# Wooby.net
KiCad netlist of a schematic drawn in EAGLE
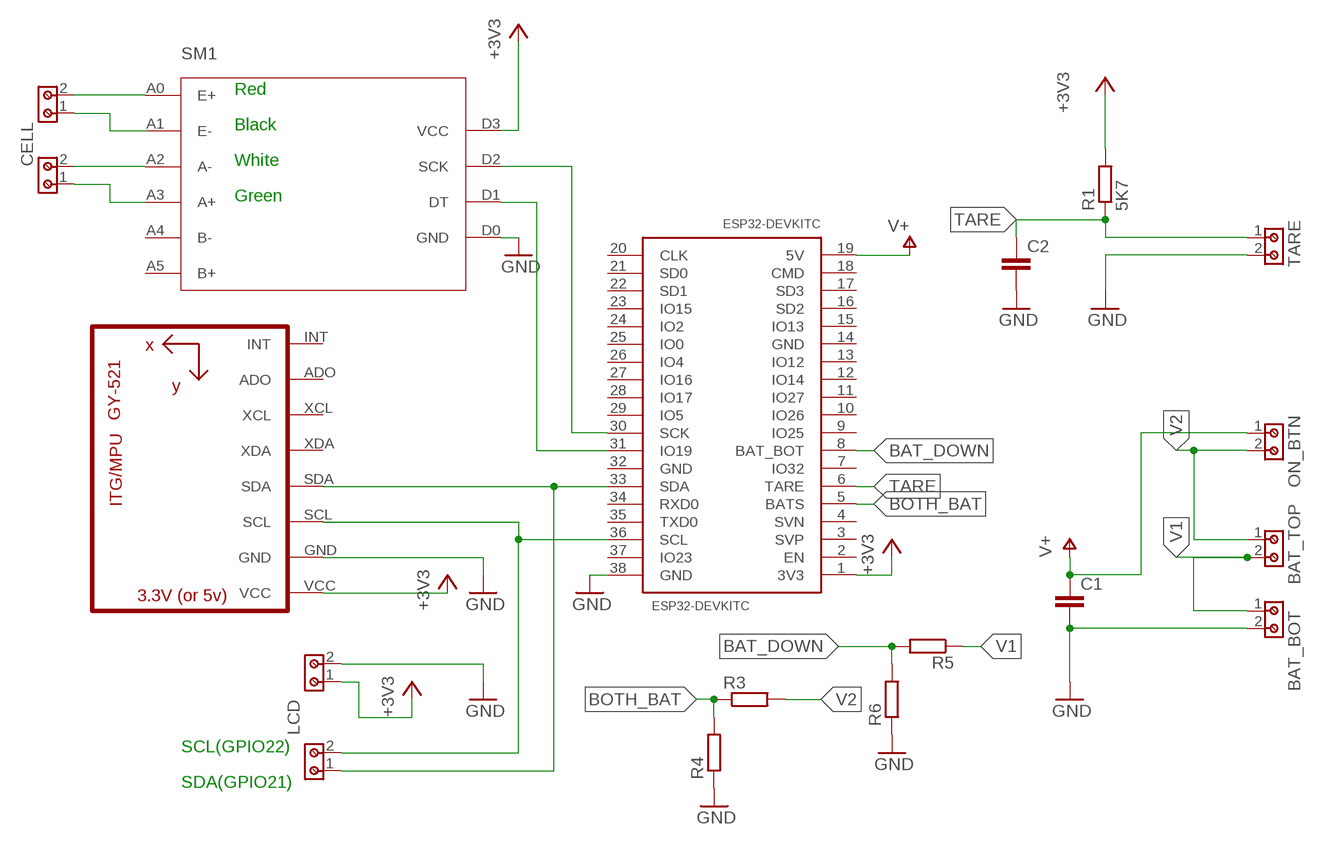
[diagram p0: schematic, sheet 1]

(export (version "E")
  (design (tool "Eeschema 10.0.6"))
  (components
    (comp (ref "BAT_BOT")
      (value "691210910002")
      (footprint "eagle-import:691210910002")
      (fields (field (name "MF") "Würth Elektronik"))
      (libsource (lib "eagle-import") (part "691210910002"))
    )
    (comp (ref "BAT_TOP")
      (value "691210910002")
      (footprint "eagle-import:691210910002")
      (fields (field (name "MF") "Würth Elektronik"))
      (libsource (lib "eagle-import") (part "691210910002"))
    )
    (comp (ref "C1")
      (value "C5/3")
      (footprint "eagle-import:C5B3")
      (libsource (lib "eagle-import") (part "C5/3"))
    )
    (comp (ref "C2")
      (value "C5/3")
      (footprint "eagle-import:C5B3")
      (libsource (lib "eagle-import") (part "C5/3"))
    )
    (comp (ref "CELL")
      (value "691210910002")
      (footprint "eagle-import:691210910002")
      (fields (field (name "MF") "Würth Elektronik"))
      (libsource (lib "eagle-import") (part "691210910002"))
    )
    (comp (ref "ESP32-DEVKITC")
      (value "ESP32DEVKITC")
      (footprint "eagle-import:ESP32-DEVKITC")
      (libsource (lib "eagle-import") (part "ESP32DEVKITC"))
    )
    (comp (ref "J2")
      (value "691210910002")
      (footprint "eagle-import:691210910002")
      (fields (field (name "MF") "Würth Elektronik"))
      (libsource (lib "eagle-import") (part "691210910002"))
    )
    (comp (ref "J5")
      (value "691210910002")
      (footprint "eagle-import:691210910002")
      (fields (field (name "MF") "Würth Elektronik"))
      (libsource (lib "eagle-import") (part "691210910002"))
    )
    (comp (ref "LCD")
      (value "691210910002")
      (footprint "eagle-import:691210910002")
      (fields (field (name "MF") "Würth Elektronik"))
      (libsource (lib "eagle-import") (part "691210910002"))
    )
    (comp (ref "ON_BTN")
      (value "691210910002")
      (footprint "eagle-import:691210910002")
      (fields (field (name "MF") "Würth Elektronik"))
      (libsource (lib "eagle-import") (part "691210910002"))
    )
    (comp (ref "R1")
      (value "5K7")
      (footprint "eagle-import:0207_10")
      (libsource (lib "eagle-import") (part "R-EU_0207/10"))
    )
    (comp (ref "R3")
      (value "R-EU_0207/10")
      (footprint "eagle-import:0207_10")
      (libsource (lib "eagle-import") (part "R-EU_0207/10"))
    )
    (comp (ref "R4")
      (value "R-EU_0207/10")
      (footprint "eagle-import:0207_10")
      (libsource (lib "eagle-import") (part "R-EU_0207/10"))
    )
    (comp (ref "R5")
      (value "R-EU_0207/10")
      (footprint "eagle-import:0207_10")
      (libsource (lib "eagle-import") (part "R-EU_0207/10"))
    )
    (comp (ref "R6")
      (value "R-EU_0207/10")
      (footprint "eagle-import:0207_10")
      (libsource (lib "eagle-import") (part "R-EU_0207/10"))
    )
    (comp (ref "SM1")
      (value "HX711")
      (footprint "eagle-import:HX711")
      (libsource (lib "eagle-import") (part "HX711"))
    )
    (comp (ref "TARE")
      (value "691210910002")
      (footprint "eagle-import:691210910002")
      (fields (field (name "MF") "Würth Elektronik"))
      (libsource (lib "eagle-import") (part "691210910002"))
    )
    (comp (ref "U1")
      (value "GY-521MPU6050")
      (footprint "eagle-import:GY-521")
      (libsource (lib "eagle-import") (part "GY-521MPU6050"))
    )
  )
  (nets
    (net (code "1") (name "+3V3") (class "Default")
      (node (ref "ESP32-DEVKITC") (pin "1") (pinfunction "3V3_1") (pintype "bidirectional"))
      (node (ref "LCD") (pin "1") (pinfunction "1_1") (pintype "passive"))
      (node (ref "R1") (pin "2") (pinfunction "2_2") (pintype "passive"))
      (node (ref "SM1") (pin "D3") (pinfunction "VCC_D3") (pintype "bidirectional"))
      (node (ref "U1") (pin "VCC") (pinfunction "VCC_VCC") (pintype "bidirectional"))
    )
    (net (code "2") (name "BAT_DOWN") (class "Default")
      (node (ref "ESP32-DEVKITC") (pin "8") (pinfunction "BAT_BOT_8") (pintype "bidirectional"))
      (node (ref "R5") (pin "2") (pinfunction "2_2") (pintype "passive"))
      (node (ref "R6") (pin "2") (pinfunction "2_2") (pintype "passive"))
    )
    (net (code "3") (name "BOTH_BAT") (class "Default")
      (node (ref "ESP32-DEVKITC") (pin "5") (pinfunction "BATS_5") (pintype "bidirectional"))
      (node (ref "R3") (pin "1") (pinfunction "1_1") (pintype "passive"))
      (node (ref "R4") (pin "2") (pinfunction "2_2") (pintype "passive"))
    )
    (net (code "4") (name "GND") (class "Default")
      (node (ref "BAT_BOT") (pin "2") (pinfunction "2_2") (pintype "passive"))
      (node (ref "C1") (pin "2") (pinfunction "2_2") (pintype "passive"))
      (node (ref "C2") (pin "2") (pinfunction "2_2") (pintype "passive"))
      (node (ref "ESP32-DEVKITC") (pin "38") (pinfunction "GND_38") (pintype "bidirectional"))
      (node (ref "LCD") (pin "2") (pinfunction "2_2") (pintype "passive"))
      (node (ref "R4") (pin "1") (pinfunction "1_1") (pintype "passive"))
      (node (ref "R6") (pin "1") (pinfunction "1_1") (pintype "passive"))
      (node (ref "SM1") (pin "D0") (pinfunction "GND_D0") (pintype "bidirectional"))
      (node (ref "TARE") (pin "2") (pinfunction "2_2") (pintype "passive"))
      (node (ref "U1") (pin "GND") (pinfunction "GND_GND") (pintype "bidirectional"))
    )
    (net (code "5") (name "Net-(ESP32-DEVKITC-IO19)") (class "Default")
      (node (ref "ESP32-DEVKITC") (pin "31") (pinfunction "IO19_31") (pintype "bidirectional"))
      (node (ref "SM1") (pin "D1") (pinfunction "DT_D1") (pintype "bidirectional"))
    )
    (net (code "6") (name "Net-(ESP32-DEVKITC-SCK)") (class "Default")
      (node (ref "ESP32-DEVKITC") (pin "30") (pinfunction "SCK_30") (pintype "bidirectional"))
      (node (ref "SM1") (pin "D2") (pinfunction "SCK_D2") (pintype "bidirectional"))
    )
    (net (code "7") (name "Net-(ESP32-DEVKITC-SCL)") (class "Default")
      (node (ref "ESP32-DEVKITC") (pin "36") (pinfunction "SCL_36") (pintype "bidirectional"))
      (node (ref "J2") (pin "2") (pinfunction "2_2") (pintype "passive"))
      (node (ref "U1") (pin "SCL") (pinfunction "SCL_SCL") (pintype "bidirectional"))
    )
    (net (code "8") (name "Net-(ESP32-DEVKITC-SDA)") (class "Default")
      (node (ref "ESP32-DEVKITC") (pin "33") (pinfunction "SDA_33") (pintype "bidirectional"))
      (node (ref "J2") (pin "1") (pinfunction "1_1") (pintype "passive"))
      (node (ref "U1") (pin "SDA") (pinfunction "SDA_SDA") (pintype "bidirectional"))
    )
    (net (code "9") (name "Net-(SM1-A+)") (class "Default")
      (node (ref "J5") (pin "1") (pinfunction "1_1") (pintype "passive"))
      (node (ref "SM1") (pin "A3") (pinfunction "A+_A3") (pintype "bidirectional"))
    )
    (net (code "10") (name "Net-(SM1-A-)") (class "Default")
      (node (ref "J5") (pin "2") (pinfunction "2_2") (pintype "passive"))
      (node (ref "SM1") (pin "A2") (pinfunction "A-_A2") (pintype "bidirectional"))
    )
    (net (code "11") (name "Net-(SM1-E+)") (class "Default")
      (node (ref "CELL") (pin "2") (pinfunction "2_2") (pintype "passive"))
      (node (ref "SM1") (pin "A0") (pinfunction "E+_A0") (pintype "bidirectional"))
    )
    (net (code "12") (name "Net-(SM1-E-)") (class "Default")
      (node (ref "CELL") (pin "1") (pinfunction "1_1") (pintype "passive"))
      (node (ref "SM1") (pin "A1") (pinfunction "E-_A1") (pintype "bidirectional"))
    )
    (net (code "13") (name "TARE") (class "Default")
      (node (ref "C2") (pin "1") (pinfunction "1_1") (pintype "passive"))
      (node (ref "ESP32-DEVKITC") (pin "6") (pinfunction "TARE_6") (pintype "bidirectional"))
      (node (ref "R1") (pin "1") (pinfunction "1_1") (pintype "passive"))
      (node (ref "TARE") (pin "1") (pinfunction "1_1") (pintype "passive"))
    )
    (net (code "14") (name "V+") (class "Default")
      (node (ref "C1") (pin "1") (pinfunction "1_1") (pintype "passive"))
      (node (ref "ESP32-DEVKITC") (pin "19") (pinfunction "5V_19") (pintype "bidirectional"))
      (node (ref "ON_BTN") (pin "1") (pinfunction "1_1") (pintype "passive"))
    )
    (net (code "15") (name "V1") (class "Default")
      (node (ref "BAT_BOT") (pin "1") (pinfunction "1_1") (pintype "passive"))
      (node (ref "BAT_TOP") (pin "2") (pinfunction "2_2") (pintype "passive"))
      (node (ref "R5") (pin "1") (pinfunction "1_1") (pintype "passive"))
    )
    (net (code "16") (name "V2") (class "Default")
      (node (ref "BAT_TOP") (pin "1") (pinfunction "1_1") (pintype "passive"))
      (node (ref "ON_BTN") (pin "2") (pinfunction "2_2") (pintype "passive"))
      (node (ref "R3") (pin "2") (pinfunction "2_2") (pintype "passive"))
    )
    (net (code "17") (name "unconnected-(ESP32-DEVKITC-CLK-Pad20)") (class "Default")
      (node (ref "ESP32-DEVKITC") (pin "20") (pinfunction "CLK_20") (pintype "bidirectional"))
    )
    (net (code "18") (name "unconnected-(ESP32-DEVKITC-CMD-Pad18)") (class "Default")
      (node (ref "ESP32-DEVKITC") (pin "18") (pinfunction "CMD_18") (pintype "bidirectional"))
    )
    (net (code "19") (name "unconnected-(ESP32-DEVKITC-EN-Pad2)") (class "Default")
      (node (ref "ESP32-DEVKITC") (pin "2") (pinfunction "EN_2") (pintype "bidirectional"))
    )
    (net (code "20") (name "unconnected-(ESP32-DEVKITC-GND-Pad14)") (class "Default")
      (node (ref "ESP32-DEVKITC") (pin "14") (pinfunction "GND_14") (pintype "bidirectional"))
    )
    (net (code "21") (name "unconnected-(ESP32-DEVKITC-GND-Pad32)") (class "Default")
      (node (ref "ESP32-DEVKITC") (pin "32") (pinfunction "GND_32") (pintype "bidirectional"))
    )
    (net (code "22") (name "unconnected-(ESP32-DEVKITC-IO0-Pad25)") (class "Default")
      (node (ref "ESP32-DEVKITC") (pin "25") (pinfunction "IO0_25") (pintype "bidirectional"))
    )
    (net (code "23") (name "unconnected-(ESP32-DEVKITC-IO2-Pad24)") (class "Default")
      (node (ref "ESP32-DEVKITC") (pin "24") (pinfunction "IO2_24") (pintype "bidirectional"))
    )
    (net (code "24") (name "unconnected-(ESP32-DEVKITC-IO4-Pad26)") (class "Default")
      (node (ref "ESP32-DEVKITC") (pin "26") (pinfunction "IO4_26") (pintype "bidirectional"))
    )
    (net (code "25") (name "unconnected-(ESP32-DEVKITC-IO5-Pad29)") (class "Default")
      (node (ref "ESP32-DEVKITC") (pin "29") (pinfunction "IO5_29") (pintype "bidirectional"))
    )
    (net (code "26") (name "unconnected-(ESP32-DEVKITC-IO12-Pad13)") (class "Default")
      (node (ref "ESP32-DEVKITC") (pin "13") (pinfunction "IO12_13") (pintype "bidirectional"))
    )
    (net (code "27") (name "unconnected-(ESP32-DEVKITC-IO13-Pad15)") (class "Default")
      (node (ref "ESP32-DEVKITC") (pin "15") (pinfunction "IO13_15") (pintype "bidirectional"))
    )
    (net (code "28") (name "unconnected-(ESP32-DEVKITC-IO14-Pad12)") (class "Default")
      (node (ref "ESP32-DEVKITC") (pin "12") (pinfunction "IO14_12") (pintype "bidirectional"))
    )
    (net (code "29") (name "unconnected-(ESP32-DEVKITC-IO15-Pad23)") (class "Default")
      (node (ref "ESP32-DEVKITC") (pin "23") (pinfunction "IO15_23") (pintype "bidirectional"))
    )
    (net (code "30") (name "unconnected-(ESP32-DEVKITC-IO16-Pad27)") (class "Default")
      (node (ref "ESP32-DEVKITC") (pin "27") (pinfunction "IO16_27") (pintype "bidirectional"))
    )
    (net (code "31") (name "unconnected-(ESP32-DEVKITC-IO17-Pad28)") (class "Default")
      (node (ref "ESP32-DEVKITC") (pin "28") (pinfunction "IO17_28") (pintype "bidirectional"))
    )
    (net (code "32") (name "unconnected-(ESP32-DEVKITC-IO23-Pad37)") (class "Default")
      (node (ref "ESP32-DEVKITC") (pin "37") (pinfunction "IO23_37") (pintype "bidirectional"))
    )
    (net (code "33") (name "unconnected-(ESP32-DEVKITC-IO25-Pad9)") (class "Default")
      (node (ref "ESP32-DEVKITC") (pin "9") (pinfunction "IO25_9") (pintype "bidirectional"))
    )
    (net (code "34") (name "unconnected-(ESP32-DEVKITC-IO26-Pad10)") (class "Default")
      (node (ref "ESP32-DEVKITC") (pin "10") (pinfunction "IO26_10") (pintype "bidirectional"))
    )
    (net (code "35") (name "unconnected-(ESP32-DEVKITC-IO27-Pad11)") (class "Default")
      (node (ref "ESP32-DEVKITC") (pin "11") (pinfunction "IO27_11") (pintype "bidirectional"))
    )
    (net (code "36") (name "unconnected-(ESP32-DEVKITC-IO32-Pad7)") (class "Default")
      (node (ref "ESP32-DEVKITC") (pin "7") (pinfunction "IO32_7") (pintype "bidirectional"))
    )
    (net (code "37") (name "unconnected-(ESP32-DEVKITC-RXD0-Pad34)") (class "Default")
      (node (ref "ESP32-DEVKITC") (pin "34") (pinfunction "RXD0_34") (pintype "bidirectional"))
    )
    (net (code "38") (name "unconnected-(ESP32-DEVKITC-SD0-Pad21)") (class "Default")
      (node (ref "ESP32-DEVKITC") (pin "21") (pinfunction "SD0_21") (pintype "bidirectional"))
    )
    (net (code "39") (name "unconnected-(ESP32-DEVKITC-SD1-Pad22)") (class "Default")
      (node (ref "ESP32-DEVKITC") (pin "22") (pinfunction "SD1_22") (pintype "bidirectional"))
    )
    (net (code "40") (name "unconnected-(ESP32-DEVKITC-SD2-Pad16)") (class "Default")
      (node (ref "ESP32-DEVKITC") (pin "16") (pinfunction "SD2_16") (pintype "bidirectional"))
    )
    (net (code "41") (name "unconnected-(ESP32-DEVKITC-SD3-Pad17)") (class "Default")
      (node (ref "ESP32-DEVKITC") (pin "17") (pinfunction "SD3_17") (pintype "bidirectional"))
    )
    (net (code "42") (name "unconnected-(ESP32-DEVKITC-SVN-Pad4)") (class "Default")
      (node (ref "ESP32-DEVKITC") (pin "4") (pinfunction "SVN_4") (pintype "bidirectional"))
    )
    (net (code "43") (name "unconnected-(ESP32-DEVKITC-SVP-Pad3)") (class "Default")
      (node (ref "ESP32-DEVKITC") (pin "3") (pinfunction "SVP_3") (pintype "bidirectional"))
    )
    (net (code "44") (name "unconnected-(ESP32-DEVKITC-TXD0-Pad35)") (class "Default")
      (node (ref "ESP32-DEVKITC") (pin "35") (pinfunction "TXD0_35") (pintype "bidirectional"))
    )
    (net (code "45") (name "unconnected-(SM1-B+-PadA5)") (class "Default")
      (node (ref "SM1") (pin "A5") (pinfunction "B+_A5") (pintype "bidirectional"))
    )
    (net (code "46") (name "unconnected-(SM1-B--PadA4)") (class "Default")
      (node (ref "SM1") (pin "A4") (pinfunction "B-_A4") (pintype "bidirectional"))
    )
    (net (code "47") (name "unconnected-(U1-PadADO)") (class "Default")
      (node (ref "U1") (pin "ADO") (pinfunction "ADO_ADO") (pintype "bidirectional"))
    )
    (net (code "48") (name "unconnected-(U1-PadINT)") (class "Default")
      (node (ref "U1") (pin "INT") (pinfunction "INT_INT") (pintype "bidirectional"))
    )
    (net (code "49") (name "unconnected-(U1-PadXCL)") (class "Default")
      (node (ref "U1") (pin "XCL") (pinfunction "XCL_XCL") (pintype "bidirectional"))
    )
    (net (code "50") (name "unconnected-(U1-PadXDA)") (class "Default")
      (node (ref "U1") (pin "XDA") (pinfunction "XDA_XDA") (pintype "bidirectional"))
    )
  )
)
